# HM10-Temp.net
KiCad netlist of a schematic drawn in EAGLE
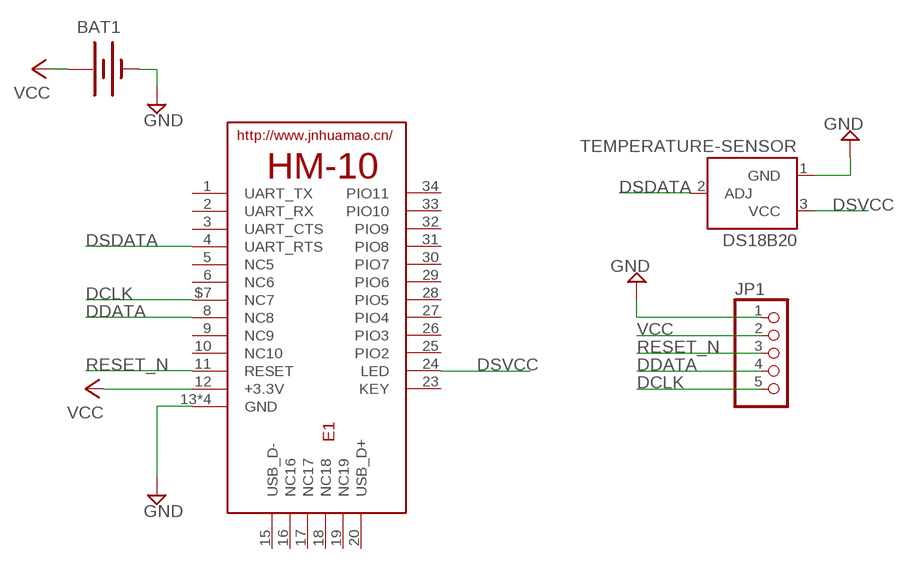
[diagram p0: schematic, sheet 1]

(export (version "E")
  (design (tool "Eeschema 10.0.6"))
  (components
    (comp (ref "BAT1")
      (value "BATTERY20PTH")
      (footprint "eagle-import:BATTCOM_20MM_PTH")
      (libsource (lib "eagle-import") (part "BATTERY20PTH"))
    )
    (comp (ref "DS18B20")
      (value "TEMPERATURE-SENSOR")
      (footprint "eagle-import:TO-92")
      (libsource (lib "eagle-import") (part "TEMPERATURE-SENSOR"))
    )
    (comp (ref "E1")
      (value "HM-10-BOARD")
      (footprint "eagle-import:26.9X13X2.2_BOARD")
      (libsource (lib "eagle-import") (part "HM-10-BOARD"))
    )
    (comp (ref "JP1")
      (value "PINHD-1X5")
      (footprint "eagle-import:1X05")
      (libsource (lib "eagle-import") (part "PINHD-1X5"))
    )
  )
  (nets
    (net (code "1") (name "/DCLK") (class "Default")
      (node (ref "E1") (pin "$7") (pinfunction "NC7_$7") (pintype "bidirectional"))
      (node (ref "JP1") (pin "5") (pinfunction "5_5") (pintype "passive"))
    )
    (net (code "2") (name "/DDATA") (class "Default")
      (node (ref "E1") (pin "8") (pinfunction "NC8_8") (pintype "bidirectional"))
      (node (ref "JP1") (pin "4") (pinfunction "4_4") (pintype "passive"))
    )
    (net (code "3") (name "/DSDATA") (class "Default")
      (node (ref "DS18B20") (pin "2") (pinfunction "ADJ_2") (pintype "bidirectional"))
      (node (ref "E1") (pin "4") (pinfunction "UART_RTS_4") (pintype "bidirectional"))
    )
    (net (code "4") (name "/DSVCC") (class "Default")
      (node (ref "DS18B20") (pin "3") (pinfunction "VCC_3") (pintype "bidirectional"))
      (node (ref "E1") (pin "24") (pinfunction "LED_24") (pintype "bidirectional"))
    )
    (net (code "5") (name "/RESET_N") (class "Default")
      (node (ref "E1") (pin "11") (pinfunction "RESET_11") (pintype "bidirectional"))
      (node (ref "JP1") (pin "3") (pinfunction "3_3") (pintype "passive"))
    )
    (net (code "6") (name "GND") (class "Default")
      (node (ref "BAT1") (pin "2") (pinfunction "-_2") (pintype "power_in"))
      (node (ref "DS18B20") (pin "1") (pinfunction "GND_1") (pintype "bidirectional"))
      (node (ref "E1") (pin "13") (pinfunction "GND_13") (pintype "bidirectional"))
      (node (ref "E1") (pin "14") (pinfunction "GND_14") (pintype "bidirectional"))
      (node (ref "E1") (pin "21") (pinfunction "GND_21") (pintype "bidirectional"))
      (node (ref "E1") (pin "22") (pinfunction "GND_22") (pintype "bidirectional"))
      (node (ref "JP1") (pin "1") (pinfunction "1_1") (pintype "passive"))
    )
    (net (code "7") (name "VCC") (class "Default")
      (node (ref "BAT1") (pin "1") (pinfunction "+_1") (pintype "power_in"))
      (node (ref "E1") (pin "12") (pinfunction "+3.3V_12") (pintype "bidirectional"))
      (node (ref "JP1") (pin "2") (pinfunction "2_2") (pintype "passive"))
    )
    (net (code "8") (name "unconnected-(E1-KEY-Pad23)") (class "Default")
      (node (ref "E1") (pin "23") (pinfunction "KEY_23") (pintype "bidirectional"))
    )
    (net (code "9") (name "unconnected-(E1-NC5-Pad5)") (class "Default")
      (node (ref "E1") (pin "5") (pinfunction "NC5_5") (pintype "bidirectional"))
    )
    (net (code "10") (name "unconnected-(E1-NC6-Pad6)") (class "Default")
      (node (ref "E1") (pin "6") (pinfunction "NC6_6") (pintype "bidirectional"))
    )
    (net (code "11") (name "unconnected-(E1-NC9-Pad9)") (class "Default")
      (node (ref "E1") (pin "9") (pinfunction "NC9_9") (pintype "bidirectional"))
    )
    (net (code "12") (name "unconnected-(E1-NC10-Pad10)") (class "Default")
      (node (ref "E1") (pin "10") (pinfunction "NC10_10") (pintype "bidirectional"))
    )
    (net (code "13") (name "unconnected-(E1-NC16-Pad16)") (class "Default")
      (node (ref "E1") (pin "16") (pinfunction "NC16_16") (pintype "bidirectional"))
    )
    (net (code "14") (name "unconnected-(E1-NC17-Pad17)") (class "Default")
      (node (ref "E1") (pin "17") (pinfunction "NC17_17") (pintype "bidirectional"))
    )
    (net (code "15") (name "unconnected-(E1-NC18-Pad18)") (class "Default")
      (node (ref "E1") (pin "18") (pinfunction "NC18_18") (pintype "bidirectional"))
    )
    (net (code "16") (name "unconnected-(E1-NC19-Pad19)") (class "Default")
      (node (ref "E1") (pin "19") (pinfunction "NC19_19") (pintype "bidirectional"))
    )
    (net (code "17") (name "unconnected-(E1-PIO2-Pad25)") (class "Default")
      (node (ref "E1") (pin "25") (pinfunction "PIO2_25") (pintype "bidirectional"))
    )
    (net (code "18") (name "unconnected-(E1-PIO3-Pad26)") (class "Default")
      (node (ref "E1") (pin "26") (pinfunction "PIO3_26") (pintype "bidirectional"))
    )
    (net (code "19") (name "unconnected-(E1-PIO4-Pad27)") (class "Default")
      (node (ref "E1") (pin "27") (pinfunction "PIO4_27") (pintype "bidirectional"))
    )
    (net (code "20") (name "unconnected-(E1-PIO5-Pad28)") (class "Default")
      (node (ref "E1") (pin "28") (pinfunction "PIO5_28") (pintype "bidirectional"))
    )
    (net (code "21") (name "unconnected-(E1-PIO6-Pad29)") (class "Default")
      (node (ref "E1") (pin "29") (pinfunction "PIO6_29") (pintype "bidirectional"))
    )
    (net (code "22") (name "unconnected-(E1-PIO7-Pad30)") (class "Default")
      (node (ref "E1") (pin "30") (pinfunction "PIO7_30") (pintype "bidirectional"))
    )
    (net (code "23") (name "unconnected-(E1-PIO8-Pad31)") (class "Default")
      (node (ref "E1") (pin "31") (pinfunction "PIO8_31") (pintype "bidirectional"))
    )
    (net (code "24") (name "unconnected-(E1-PIO9-Pad32)") (class "Default")
      (node (ref "E1") (pin "32") (pinfunction "PIO9_32") (pintype "bidirectional"))
    )
    (net (code "25") (name "unconnected-(E1-PIO10-Pad33)") (class "Default")
      (node (ref "E1") (pin "33") (pinfunction "PIO10_33") (pintype "bidirectional"))
    )
    (net (code "26") (name "unconnected-(E1-PIO11-Pad34)") (class "Default")
      (node (ref "E1") (pin "34") (pinfunction "PIO11_34") (pintype "bidirectional"))
    )
    (net (code "27") (name "unconnected-(E1-UART_CTS-Pad3)") (class "Default")
      (node (ref "E1") (pin "3") (pinfunction "UART_CTS_3") (pintype "bidirectional"))
    )
    (net (code "28") (name "unconnected-(E1-UART_RX-Pad2)") (class "Default")
      (node (ref "E1") (pin "2") (pinfunction "UART_RX_2") (pintype "bidirectional"))
    )
    (net (code "29") (name "unconnected-(E1-UART_TX-Pad1)") (class "Default")
      (node (ref "E1") (pin "1") (pinfunction "UART_TX_1") (pintype "bidirectional"))
    )
    (net (code "30") (name "unconnected-(E1-USB_D+-Pad20)") (class "Default")
      (node (ref "E1") (pin "20") (pinfunction "USB_D+_20") (pintype "bidirectional"))
    )
    (net (code "31") (name "unconnected-(E1-USB_D--Pad15)") (class "Default")
      (node (ref "E1") (pin "15") (pinfunction "USB_D-_15") (pintype "bidirectional"))
    )
  )
)
